# badge_mil.net
KiCad netlist of a schematic drawn in EAGLE
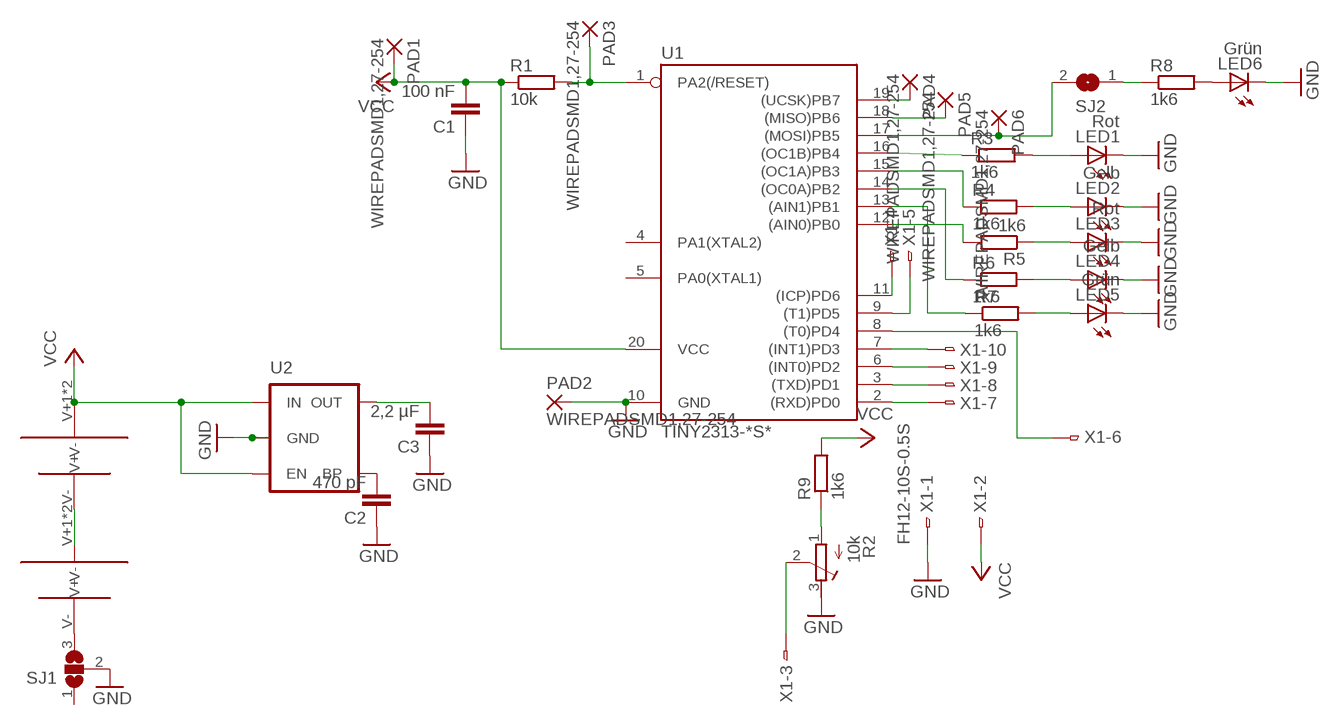
[diagram p0: schematic, sheet 1]

(export (version "E")
  (design (tool "Eeschema 10.0.6"))
  (components
    (comp (ref "C1")
      (value "100 nF")
      (footprint "eagle-import:C0805")
      (libsource (lib "eagle-import") (part "C-EUC0805"))
    )
    (comp (ref "C2")
      (value "470 pF")
      (footprint "eagle-import:C0805")
      (libsource (lib "eagle-import") (part "C-EUC0805"))
    )
    (comp (ref "C3")
      (value "2,2 µF")
      (footprint "eagle-import:C0805")
      (libsource (lib "eagle-import") (part "C-EUC0805"))
    )
    (comp (ref "LED1")
      (value "Rot")
      (footprint "eagle-import:SML0603")
      (libsource (lib "eagle-import") (part "LEDSML0603"))
    )
    (comp (ref "LED2")
      (value "Gelb")
      (footprint "eagle-import:SML0603")
      (libsource (lib "eagle-import") (part "LEDSML0603"))
    )
    (comp (ref "LED3")
      (value "Rot")
      (footprint "eagle-import:SML0603")
      (libsource (lib "eagle-import") (part "LEDSML0603"))
    )
    (comp (ref "LED4")
      (value "Gelb")
      (footprint "eagle-import:SML0603")
      (libsource (lib "eagle-import") (part "LEDSML0603"))
    )
    (comp (ref "LED5")
      (value "Grün")
      (footprint "eagle-import:SML0603")
      (libsource (lib "eagle-import") (part "LEDSML0603"))
    )
    (comp (ref "LED6")
      (value "Grün")
      (footprint "eagle-import:SML0603")
      (libsource (lib "eagle-import") (part "LEDSML0603"))
    )
    (comp (ref "PAD1")
      (value "WIREPADSMD1,27-254")
      (footprint "eagle-import:SMD1,27-2,54")
      (libsource (lib "eagle-import") (part "WIREPADSMD1,27-254"))
    )
    (comp (ref "PAD2")
      (value "WIREPADSMD1,27-254")
      (footprint "eagle-import:SMD1,27-2,54")
      (libsource (lib "eagle-import") (part "WIREPADSMD1,27-254"))
    )
    (comp (ref "PAD3")
      (value "WIREPADSMD1,27-254")
      (footprint "eagle-import:SMD1,27-2,54")
      (libsource (lib "eagle-import") (part "WIREPADSMD1,27-254"))
    )
    (comp (ref "PAD4")
      (value "WIREPADSMD1,27-254")
      (footprint "eagle-import:SMD1,27-2,54")
      (libsource (lib "eagle-import") (part "WIREPADSMD1,27-254"))
    )
    (comp (ref "PAD5")
      (value "WIREPADSMD1,27-254")
      (footprint "eagle-import:SMD1,27-2,54")
      (libsource (lib "eagle-import") (part "WIREPADSMD1,27-254"))
    )
    (comp (ref "PAD6")
      (value "WIREPADSMD1,27-254")
      (footprint "eagle-import:SMD1,27-2,54")
      (libsource (lib "eagle-import") (part "WIREPADSMD1,27-254"))
    )
    (comp (ref "R1")
      (value "10k")
      (footprint "eagle-import:R0805")
      (libsource (lib "eagle-import") (part "R-EU_R0805"))
    )
    (comp (ref "R2")
      (value "10k")
      (footprint "eagle-import:RTRIM4G_J")
      (libsource (lib "eagle-import") (part "R-TRIMM4G/J"))
    )
    (comp (ref "R3")
      (value "1k6")
      (footprint "eagle-import:R0805")
      (libsource (lib "eagle-import") (part "R-EU_R0805"))
    )
    (comp (ref "R4")
      (value "1k6")
      (footprint "eagle-import:R0805")
      (libsource (lib "eagle-import") (part "R-EU_R0805"))
    )
    (comp (ref "R5")
      (value "1k6")
      (footprint "eagle-import:R0805")
      (libsource (lib "eagle-import") (part "R-EU_R0805"))
    )
    (comp (ref "R6")
      (value "1k6")
      (footprint "eagle-import:R0805")
      (libsource (lib "eagle-import") (part "R-EU_R0805"))
    )
    (comp (ref "R7")
      (value "1k6")
      (footprint "eagle-import:R0805")
      (libsource (lib "eagle-import") (part "R-EU_R0805"))
    )
    (comp (ref "R8")
      (value "1k6")
      (footprint "eagle-import:R0805")
      (libsource (lib "eagle-import") (part "R-EU_R0805"))
    )
    (comp (ref "R9")
      (value "1k6")
      (footprint "eagle-import:R0805")
      (libsource (lib "eagle-import") (part "R-EU_R0805"))
    )
    (comp (ref "SJ1")
      (value "SJ2WW")
      (footprint "eagle-import:SJ_2W")
      (libsource (lib "eagle-import") (part "SJ2WW"))
    )
    (comp (ref "SJ2")
      (value "SJW")
      (footprint "eagle-import:SJW")
      (libsource (lib "eagle-import") (part "SJW"))
    )
    (comp (ref "U$1")
      (value "KEYSTONE3002")
      (footprint "eagle-import:KEYSTONE3002")
      (libsource (lib "eagle-import") (part "KEYSTONE3002"))
    )
    (comp (ref "U$2")
      (value "KEYSTONE3002")
      (footprint "eagle-import:KEYSTONE3002")
      (libsource (lib "eagle-import") (part "KEYSTONE3002"))
    )
    (comp (ref "U1")
      (value "TINY2313-*S*")
      (footprint "eagle-import:SO20L$")
      (libsource (lib "eagle-import") (part "TINY2313-S"))
    )
    (comp (ref "U2")
      (value "MIC52055V")
      (footprint "eagle-import:SOT23-5")
      (libsource (lib "eagle-import") (part "MIC52055V"))
    )
    (comp (ref "X1")
      (value "FH12-10S-0.5S")
      (footprint "eagle-import:FH12-10S-1.0SH")
      (libsource (lib "eagle-import") (part "FH12-10S-0.5S"))
    )
  )
  (nets
    (net (code "1") (name "GND") (class "Default")
      (node (ref "C1") (pin "1") (pinfunction "1_1") (pintype "passive"))
      (node (ref "C2") (pin "1") (pinfunction "1_1") (pintype "passive"))
      (node (ref "C3") (pin "1") (pinfunction "1_1") (pintype "passive"))
      (node (ref "LED1") (pin "C") (pinfunction "C_C") (pintype "passive"))
      (node (ref "LED2") (pin "C") (pinfunction "C_C") (pintype "passive"))
      (node (ref "LED3") (pin "C") (pinfunction "C_C") (pintype "passive"))
      (node (ref "LED4") (pin "C") (pinfunction "C_C") (pintype "passive"))
      (node (ref "LED5") (pin "C") (pinfunction "C_C") (pintype "passive"))
      (node (ref "LED6") (pin "C") (pinfunction "C_C") (pintype "passive"))
      (node (ref "PAD2") (pin "1") (pinfunction "P_1") (pintype "passive"))
      (node (ref "R2") (pin "3") (pinfunction "A_3") (pintype "passive"))
      (node (ref "SJ1") (pin "2") (pinfunction "2_2") (pintype "passive"))
      (node (ref "U1") (pin "10") (pinfunction "GND_10") (pintype "power_in"))
      (node (ref "U2") (pin "2") (pinfunction "GND_2") (pintype "input"))
      (node (ref "X1") (pin "1") (pinfunction "1_1") (pintype "passive"))
    )
    (net (code "2") (name "Net-(LED1-PadA)") (class "Default")
      (node (ref "LED1") (pin "A") (pinfunction "A_A") (pintype "passive"))
      (node (ref "R3") (pin "2") (pinfunction "2_2") (pintype "passive"))
    )
    (net (code "3") (name "Net-(LED2-PadA)") (class "Default")
      (node (ref "LED2") (pin "A") (pinfunction "A_A") (pintype "passive"))
      (node (ref "R4") (pin "2") (pinfunction "2_2") (pintype "passive"))
    )
    (net (code "4") (name "Net-(LED3-PadA)") (class "Default")
      (node (ref "LED3") (pin "A") (pinfunction "A_A") (pintype "passive"))
      (node (ref "R5") (pin "1") (pinfunction "1_1") (pintype "passive"))
    )
    (net (code "5") (name "Net-(LED4-PadA)") (class "Default")
      (node (ref "LED4") (pin "A") (pinfunction "A_A") (pintype "passive"))
      (node (ref "R6") (pin "2") (pinfunction "2_2") (pintype "passive"))
    )
    (net (code "6") (name "Net-(LED5-PadA)") (class "Default")
      (node (ref "LED5") (pin "A") (pinfunction "A_A") (pintype "passive"))
      (node (ref "R7") (pin "2") (pinfunction "2_2") (pintype "passive"))
    )
    (net (code "7") (name "Net-(LED6-PadA)") (class "Default")
      (node (ref "LED6") (pin "A") (pinfunction "A_A") (pintype "passive"))
      (node (ref "R8") (pin "2") (pinfunction "2_2") (pintype "passive"))
    )
    (net (code "8") (name "Net-(PAD3-P)") (class "Default")
      (node (ref "PAD3") (pin "1") (pinfunction "P_1") (pintype "passive"))
      (node (ref "R1") (pin "2") (pinfunction "2_2") (pintype "passive"))
      (node (ref "U1") (pin "1") (pinfunction "PA2(/RESET)_1") (pintype "input"))
    )
    (net (code "9") (name "Net-(PAD4-P)") (class "Default")
      (node (ref "PAD4") (pin "1") (pinfunction "P_1") (pintype "passive"))
      (node (ref "U1") (pin "19") (pinfunction "(UCSK)PB7_19") (pintype "bidirectional"))
    )
    (net (code "10") (name "Net-(PAD5-P)") (class "Default")
      (node (ref "PAD5") (pin "1") (pinfunction "P_1") (pintype "passive"))
      (node (ref "U1") (pin "18") (pinfunction "(MISO)PB6_18") (pintype "bidirectional"))
    )
    (net (code "11") (name "Net-(PAD6-P)") (class "Default")
      (node (ref "PAD6") (pin "1") (pinfunction "P_1") (pintype "passive"))
      (node (ref "SJ2") (pin "2") (pinfunction "2_2") (pintype "passive"))
      (node (ref "U1") (pin "17") (pinfunction "(MOSI)PB5_17") (pintype "bidirectional"))
    )
    (net (code "12") (name "Net-(R2-E)") (class "Default")
      (node (ref "R2") (pin "1") (pinfunction "E_1") (pintype "passive"))
      (node (ref "R9") (pin "1") (pinfunction "1_1") (pintype "passive"))
    )
    (net (code "13") (name "Net-(R2-S)") (class "Default")
      (node (ref "R2") (pin "2") (pinfunction "S_2") (pintype "passive"))
      (node (ref "X1") (pin "3") (pinfunction "1_3") (pintype "passive"))
    )
    (net (code "14") (name "Net-(R8-Pad1)") (class "Default")
      (node (ref "R8") (pin "1") (pinfunction "1_1") (pintype "passive"))
      (node (ref "SJ2") (pin "1") (pinfunction "1_1") (pintype "passive"))
    )
    (net (code "15") (name "Net-(SJ1-Pad3)") (class "Default")
      (node (ref "SJ1") (pin "3") (pinfunction "3_3") (pintype "passive"))
      (node (ref "U$2") (pin "V-") (pinfunction "V-_V-") (pintype "bidirectional"))
    )
    (net (code "16") (name "Net-(U$1-PadV-)") (class "Default")
      (node (ref "U$1") (pin "V-") (pinfunction "V-_V-") (pintype "bidirectional"))
      (node (ref "U$2") (pin "V+1") (pinfunction "V+_V+1") (pintype "bidirectional"))
      (node (ref "U$2") (pin "V+2") (pinfunction "V+_V+2") (pintype "bidirectional"))
    )
    (net (code "17") (name "Net-(U1-(AIN0)PB0)") (class "Default")
      (node (ref "R5") (pin "2") (pinfunction "2_2") (pintype "passive"))
      (node (ref "U1") (pin "12") (pinfunction "(AIN0)PB0_12") (pintype "bidirectional"))
    )
    (net (code "18") (name "Net-(U1-(AIN1)PB1)") (class "Default")
      (node (ref "R7") (pin "1") (pinfunction "1_1") (pintype "passive"))
      (node (ref "U1") (pin "13") (pinfunction "(AIN1)PB1_13") (pintype "bidirectional"))
    )
    (net (code "19") (name "Net-(U1-(ICP)PD6)") (class "Default")
      (node (ref "U1") (pin "11") (pinfunction "(ICP)PD6_11") (pintype "bidirectional"))
      (node (ref "X1") (pin "4") (pinfunction "1_4") (pintype "passive"))
    )
    (net (code "20") (name "Net-(U1-(INT0)PD2)") (class "Default")
      (node (ref "U1") (pin "6") (pinfunction "(INT0)PD2_6") (pintype "bidirectional"))
      (node (ref "X1") (pin "9") (pinfunction "1_9") (pintype "passive"))
    )
    (net (code "21") (name "Net-(U1-(INT1)PD3)") (class "Default")
      (node (ref "U1") (pin "7") (pinfunction "(INT1)PD3_7") (pintype "bidirectional"))
      (node (ref "X1") (pin "10") (pinfunction "1_10") (pintype "passive"))
    )
    (net (code "22") (name "Net-(U1-(OC0A)PB2)") (class "Default")
      (node (ref "R6") (pin "1") (pinfunction "1_1") (pintype "passive"))
      (node (ref "U1") (pin "14") (pinfunction "(OC0A)PB2_14") (pintype "bidirectional"))
    )
    (net (code "23") (name "Net-(U1-(OC1A)PB3)") (class "Default")
      (node (ref "R4") (pin "1") (pinfunction "1_1") (pintype "passive"))
      (node (ref "U1") (pin "15") (pinfunction "(OC1A)PB3_15") (pintype "bidirectional"))
    )
    (net (code "24") (name "Net-(U1-(OC1B)PB4)") (class "Default")
      (node (ref "R3") (pin "1") (pinfunction "1_1") (pintype "passive"))
      (node (ref "U1") (pin "16") (pinfunction "(OC1B)PB4_16") (pintype "bidirectional"))
    )
    (net (code "25") (name "Net-(U1-(RXD)PD0)") (class "Default")
      (node (ref "U1") (pin "2") (pinfunction "(RXD)PD0_2") (pintype "bidirectional"))
      (node (ref "X1") (pin "7") (pinfunction "1_7") (pintype "passive"))
    )
    (net (code "26") (name "Net-(U1-(T0)PD4)") (class "Default")
      (node (ref "U1") (pin "8") (pinfunction "(T0)PD4_8") (pintype "bidirectional"))
      (node (ref "X1") (pin "6") (pinfunction "1_6") (pintype "passive"))
    )
    (net (code "27") (name "Net-(U1-(T1)PD5)") (class "Default")
      (node (ref "U1") (pin "9") (pinfunction "(T1)PD5_9") (pintype "bidirectional"))
      (node (ref "X1") (pin "5") (pinfunction "1_5") (pintype "passive"))
    )
    (net (code "28") (name "Net-(U1-(TXD)PD1)") (class "Default")
      (node (ref "U1") (pin "3") (pinfunction "(TXD)PD1_3") (pintype "bidirectional"))
      (node (ref "X1") (pin "8") (pinfunction "1_8") (pintype "passive"))
    )
    (net (code "29") (name "Net-(U2-BP)") (class "Default")
      (node (ref "C2") (pin "2") (pinfunction "2_2") (pintype "passive"))
      (node (ref "U2") (pin "4") (pinfunction "BP_4") (pintype "input"))
    )
    (net (code "30") (name "Net-(U2-OUT)") (class "Default")
      (node (ref "C3") (pin "2") (pinfunction "2_2") (pintype "passive"))
      (node (ref "U2") (pin "5") (pinfunction "OUT_5") (pintype "passive"))
    )
    (net (code "31") (name "VCC") (class "Default")
      (node (ref "C1") (pin "2") (pinfunction "2_2") (pintype "passive"))
      (node (ref "PAD1") (pin "1") (pinfunction "P_1") (pintype "passive"))
      (node (ref "R1") (pin "1") (pinfunction "1_1") (pintype "passive"))
      (node (ref "R9") (pin "2") (pinfunction "2_2") (pintype "passive"))
      (node (ref "U$1") (pin "V+1") (pinfunction "V+_V+1") (pintype "bidirectional"))
      (node (ref "U$1") (pin "V+2") (pinfunction "V+_V+2") (pintype "bidirectional"))
      (node (ref "U1") (pin "20") (pinfunction "VCC_20") (pintype "power_in"))
      (node (ref "U2") (pin "1") (pinfunction "IN_1") (pintype "input"))
      (node (ref "U2") (pin "3") (pinfunction "EN_3") (pintype "input"))
      (node (ref "X1") (pin "2") (pinfunction "1_2") (pintype "passive"))
    )
    (net (code "32") (name "unconnected-(SJ1-Pad1)") (class "Default")
      (node (ref "SJ1") (pin "1") (pinfunction "1_1") (pintype "passive"))
    )
    (net (code "33") (name "unconnected-(U1-PA0(XTAL1)-Pad5)") (class "Default")
      (node (ref "U1") (pin "5") (pinfunction "PA0(XTAL1)_5") (pintype "bidirectional"))
    )
    (net (code "34") (name "unconnected-(U1-PA1(XTAL2)-Pad4)") (class "Default")
      (node (ref "U1") (pin "4") (pinfunction "PA1(XTAL2)_4") (pintype "bidirectional"))
    )
  )
)
